# ptmini.net
KiCad netlist of a schematic drawn in EAGLE
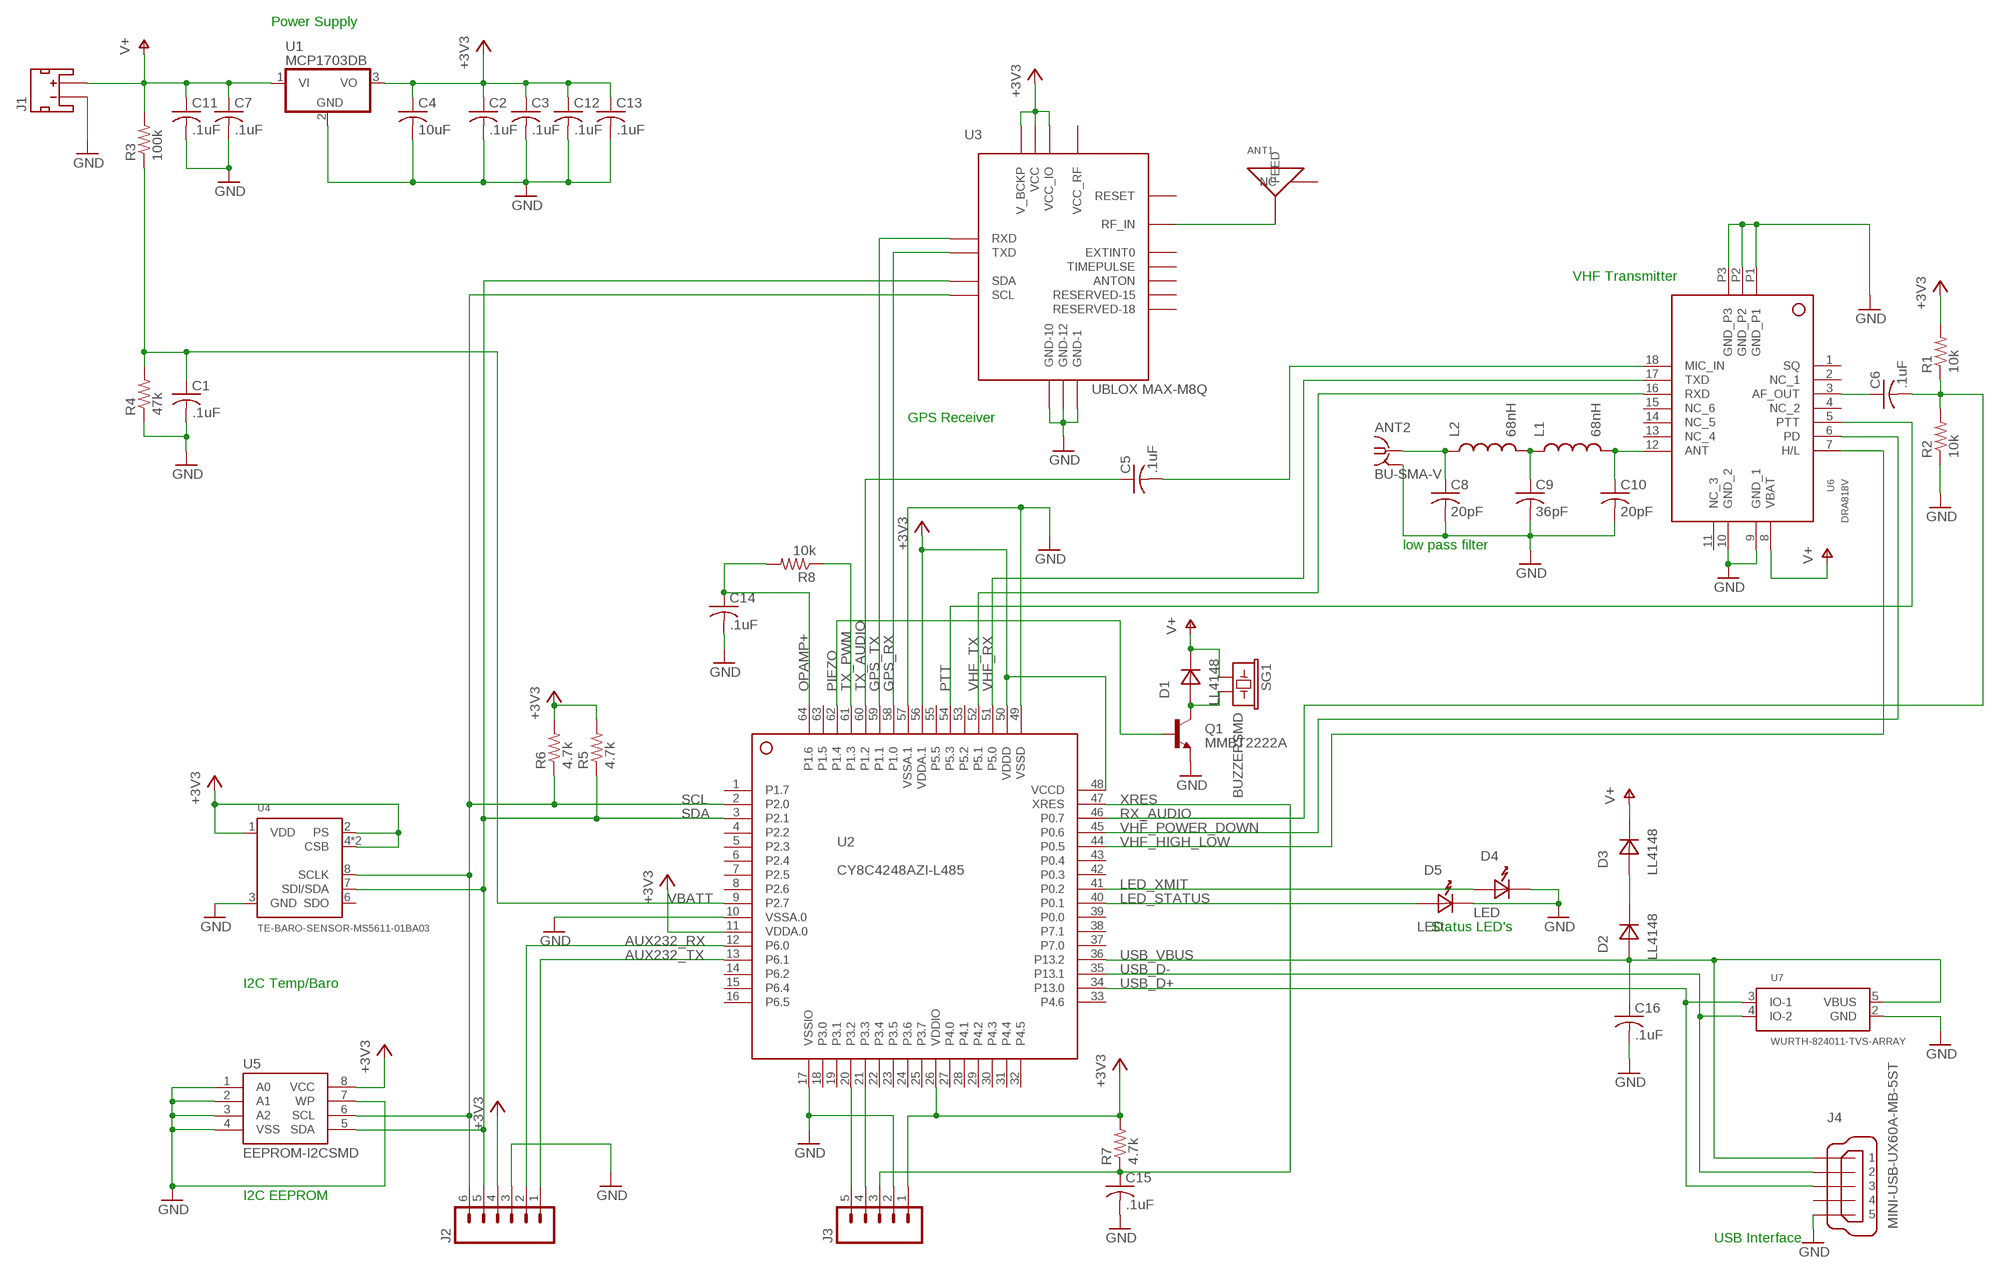
[diagram p0: schematic, sheet 1]

(export (version "E")
  (design (tool "Eeschema 10.0.6"))
  (components
    (comp (ref "ANT1")
      (value "GPS_ANT_SMDBAR")
      (footprint "eagle-import:1575AT43A40")
      (libsource (lib "eagle-import") (part "GPS_ANT_SMDBAR"))
    )
    (comp (ref "ANT2")
      (value "BU-SMA-V")
      (footprint "eagle-import:BU-SMA-V")
      (libsource (lib "eagle-import") (part "BU-SMA-V"))
    )
    (comp (ref "C1")
      (value ".1uF")
      (footprint "eagle-import:C0805")
      (libsource (lib "eagle-import") (part "C-USC0805"))
    )
    (comp (ref "C2")
      (value ".1uF")
      (footprint "eagle-import:C0805")
      (libsource (lib "eagle-import") (part "C-USC0805"))
    )
    (comp (ref "C3")
      (value ".1uF")
      (footprint "eagle-import:C0805")
      (libsource (lib "eagle-import") (part "C-USC0805"))
    )
    (comp (ref "C4")
      (value "10uF")
      (footprint "eagle-import:C0805")
      (libsource (lib "eagle-import") (part "C-USC0805"))
    )
    (comp (ref "C5")
      (value ".1uF")
      (footprint "eagle-import:C0805")
      (libsource (lib "eagle-import") (part "C-USC0805"))
    )
    (comp (ref "C6")
      (value ".1uF")
      (footprint "eagle-import:C0805")
      (libsource (lib "eagle-import") (part "C-USC0805"))
    )
    (comp (ref "C7")
      (value ".1uF")
      (footprint "eagle-import:C0805")
      (libsource (lib "eagle-import") (part "C-USC0805"))
    )
    (comp (ref "C8")
      (value "20pF")
      (footprint "eagle-import:C0805")
      (libsource (lib "eagle-import") (part "C-USC0805"))
    )
    (comp (ref "C9")
      (value "36pF")
      (footprint "eagle-import:C0805")
      (libsource (lib "eagle-import") (part "C-USC0805"))
    )
    (comp (ref "C10")
      (value "20pF")
      (footprint "eagle-import:C0805")
      (libsource (lib "eagle-import") (part "C-USC0805"))
    )
    (comp (ref "C11")
      (value ".1uF")
      (footprint "eagle-import:C0805")
      (libsource (lib "eagle-import") (part "C-USC0805"))
    )
    (comp (ref "C12")
      (value ".1uF")
      (footprint "eagle-import:C0805")
      (libsource (lib "eagle-import") (part "C-USC0805"))
    )
    (comp (ref "C13")
      (value ".1uF")
      (footprint "eagle-import:C0805")
      (libsource (lib "eagle-import") (part "C-USC0805"))
    )
    (comp (ref "C14")
      (value ".1uF")
      (footprint "eagle-import:C0805")
      (libsource (lib "eagle-import") (part "C-USC0805"))
    )
    (comp (ref "C15")
      (value ".1uF")
      (footprint "eagle-import:C0805")
      (libsource (lib "eagle-import") (part "C-USC0805"))
    )
    (comp (ref "C16")
      (value ".1uF")
      (footprint "eagle-import:C0805")
      (libsource (lib "eagle-import") (part "C-USC0805"))
    )
    (comp (ref "D1")
      (value "LL4148")
      (footprint "eagle-import:SOD-80")
      (libsource (lib "eagle-import") (part "LL4148"))
    )
    (comp (ref "D2")
      (value "LL4148")
      (footprint "eagle-import:SOD-80")
      (libsource (lib "eagle-import") (part "LL4148"))
    )
    (comp (ref "D3")
      (value "LL4148")
      (footprint "eagle-import:SOD-80")
      (libsource (lib "eagle-import") (part "LL4148"))
    )
    (comp (ref "D4")
      (value "LED")
      (footprint "eagle-import:DIODE-1206")
      (libsource (lib "eagle-import") (part "LED"))
    )
    (comp (ref "D5")
      (value "LED")
      (footprint "eagle-import:DIODE-1206")
      (libsource (lib "eagle-import") (part "LED"))
    )
    (comp (ref "J1")
      (value "JST_2MM_MALE")
      (footprint "eagle-import:JST-2-SMD")
      (libsource (lib "eagle-import") (part "JST_2MM_MALE"))
    )
    (comp (ref "J2")
      (value "M06RA")
      (footprint "eagle-import:MOLEX-1X6-RA")
      (libsource (lib "eagle-import") (part "M06RA"))
    )
    (comp (ref "J3")
      (value "M05LOCK")
      (footprint "eagle-import:1X05_LOCK")
      (libsource (lib "eagle-import") (part "M05LOCK"))
    )
    (comp (ref "J4")
      (value "MINI-USB-UX60A-MB-5ST")
      (footprint "eagle-import:UX60A-MB-5ST")
      (libsource (lib "eagle-import") (part "MINI-USB-UX60A-MB-5ST"))
    )
    (comp (ref "L1")
      (value "68nH")
      (footprint "eagle-import:0805")
      (libsource (lib "eagle-import") (part "INDUCTOR0805"))
    )
    (comp (ref "L2")
      (value "68nH")
      (footprint "eagle-import:0805")
      (libsource (lib "eagle-import") (part "INDUCTOR0805"))
    )
    (comp (ref "Q1")
      (value "MMBT2222A")
      (footprint "eagle-import:SOT23")
      (libsource (lib "eagle-import") (part "TRANSISTOR_NPNMMBT2222A"))
    )
    (comp (ref "R1")
      (value "10k")
      (footprint "eagle-import:R0805")
      (libsource (lib "eagle-import") (part "R-US_R0805"))
    )
    (comp (ref "R2")
      (value "10k")
      (footprint "eagle-import:R0805")
      (libsource (lib "eagle-import") (part "R-US_R0805"))
    )
    (comp (ref "R3")
      (value "100k")
      (footprint "eagle-import:R0805")
      (libsource (lib "eagle-import") (part "R-US_R0805"))
    )
    (comp (ref "R4")
      (value "47k")
      (footprint "eagle-import:R0805")
      (libsource (lib "eagle-import") (part "R-US_R0805"))
    )
    (comp (ref "R5")
      (value "4.7k")
      (footprint "eagle-import:R0805")
      (libsource (lib "eagle-import") (part "R-US_R0805"))
    )
    (comp (ref "R6")
      (value "4.7k")
      (footprint "eagle-import:R0805")
      (libsource (lib "eagle-import") (part "R-US_R0805"))
    )
    (comp (ref "R7")
      (value "4.7k")
      (footprint "eagle-import:R0805")
      (libsource (lib "eagle-import") (part "R-US_R0805"))
    )
    (comp (ref "R8")
      (value "10k")
      (footprint "eagle-import:R0805")
      (libsource (lib "eagle-import") (part "R-US_R0805"))
    )
    (comp (ref "SG1")
      (value "BUZZERSMD")
      (footprint "eagle-import:BUZZER-CMT1603")
      (libsource (lib "eagle-import") (part "BUZZERSMD"))
    )
    (comp (ref "U1")
      (value "MCP1703DB")
      (footprint "eagle-import:SOT223")
      (libsource (lib "eagle-import") (part "MCP1703DB"))
    )
    (comp (ref "U2")
      (value "CY8C4248AZI-L485")
      (footprint "eagle-import:TQFP64-10X10")
      (libsource (lib "eagle-import") (part "CY8C4248AZI-L485"))
    )
    (comp (ref "U3")
      (value "UBLOX MAX-M8Q")
      (footprint "eagle-import:UBLOX-MAX")
      (libsource (lib "eagle-import") (part "UBLOX-MAX"))
    )
    (comp (ref "U4")
      (value "TE-BARO-SENSOR-MS5611-01BA03")
      (footprint "eagle-import:TE-BARO-SENSOR-MS5611-01BA3")
      (libsource (lib "eagle-import") (part "TE-BARO-SENSOR-MS5611-01BA03"))
    )
    (comp (ref "U5")
      (value "EEPROM-I2CSMD")
      (footprint "eagle-import:SO08")
      (libsource (lib "eagle-import") (part "EEPROM-I2CSMD"))
    )
    (comp (ref "U6")
      (value "DRA818V")
      (footprint "eagle-import:SMD_DRA818")
      (libsource (lib "eagle-import") (part "DRA818V"))
    )
    (comp (ref "U7")
      (value "WURTH-824011-TVS-ARRAY")
      (footprint "eagle-import:SOT23-5")
      (libsource (lib "eagle-import") (part "WURTH-824011-TVS-ARRAY"))
    )
  )
  (nets
    (net (code "1") (name "+3V3") (class "Default")
      (node (ref "C12") (pin "1") (pinfunction "1_1") (pintype "passive"))
      (node (ref "C13") (pin "1") (pinfunction "1_1") (pintype "passive"))
      (node (ref "C2") (pin "1") (pinfunction "1_1") (pintype "passive"))
      (node (ref "C3") (pin "1") (pinfunction "1_1") (pintype "passive"))
      (node (ref "C4") (pin "1") (pinfunction "1_1") (pintype "passive"))
      (node (ref "J2") (pin "4") (pinfunction "4_4") (pintype "passive"))
      (node (ref "J3") (pin "1") (pinfunction "1_1") (pintype "passive"))
      (node (ref "R1") (pin "2") (pinfunction "2_2") (pintype "passive"))
      (node (ref "R5") (pin "2") (pinfunction "2_2") (pintype "passive"))
      (node (ref "R6") (pin "2") (pinfunction "2_2") (pintype "passive"))
      (node (ref "R7") (pin "2") (pinfunction "2_2") (pintype "passive"))
      (node (ref "U1") (pin "3") (pinfunction "VO_3") (pintype "passive"))
      (node (ref "U2") (pin "11") (pinfunction "VDDA.0_11") (pintype "power_in"))
      (node (ref "U2") (pin "26") (pinfunction "VDDIO_26") (pintype "power_in"))
      (node (ref "U2") (pin "48") (pinfunction "VCCD_48") (pintype "power_in"))
      (node (ref "U2") (pin "50") (pinfunction "VDDD_50") (pintype "power_in"))
      (node (ref "U2") (pin "56") (pinfunction "VDDA.1_56") (pintype "power_in"))
      (node (ref "U3") (pin "6_V_BCKP") (pinfunction "V_BCKP_6_V_BCKP") (pintype "bidirectional"))
      (node (ref "U3") (pin "7_VCC_IO") (pinfunction "VCC_IO_7_VCC_IO") (pintype "power_in"))
      (node (ref "U3") (pin "8_VCC") (pinfunction "VCC_8_VCC") (pintype "power_in"))
      (node (ref "U4") (pin "1") (pinfunction "VDD_1") (pintype "power_in"))
      (node (ref "U4") (pin "2") (pinfunction "PS_2") (pintype "bidirectional"))
      (node (ref "U4") (pin "4") (pinfunction "CSB_4") (pintype "bidirectional"))
      (node (ref "U4") (pin "5") (pinfunction "CSB_5") (pintype "bidirectional"))
      (node (ref "U5") (pin "8") (pinfunction "VCC_8") (pintype "power_in"))
    )
    (net (code "2") (name "/AUX232_RX") (class "Default")
      (node (ref "J2") (pin "2") (pinfunction "2_2") (pintype "passive"))
      (node (ref "U2") (pin "12") (pinfunction "P6.0_12") (pintype "bidirectional"))
    )
    (net (code "3") (name "/AUX232_TX") (class "Default")
      (node (ref "J2") (pin "1") (pinfunction "1_1") (pintype "passive"))
      (node (ref "U2") (pin "13") (pinfunction "P6.1_13") (pintype "bidirectional"))
    )
    (net (code "4") (name "/GPS_RX") (class "Default")
      (node (ref "U2") (pin "58") (pinfunction "P1.0_58") (pintype "bidirectional"))
      (node (ref "U3") (pin "2_TXD1") (pinfunction "TXD_2_TXD1") (pintype "bidirectional"))
    )
    (net (code "5") (name "/GPS_TX") (class "Default")
      (node (ref "U2") (pin "59") (pinfunction "P1.1_59") (pintype "bidirectional"))
      (node (ref "U3") (pin "3_RXD1") (pinfunction "RXD_3_RXD1") (pintype "bidirectional"))
    )
    (net (code "6") (name "/LED_STATUS") (class "Default")
      (node (ref "D5") (pin "ANODE") (pinfunction "ANODE_ANODE") (pintype "passive"))
      (node (ref "U2") (pin "40") (pinfunction "P0.1_40") (pintype "bidirectional"))
    )
    (net (code "7") (name "/LED_XMIT") (class "Default")
      (node (ref "D4") (pin "ANODE") (pinfunction "ANODE_ANODE") (pintype "passive"))
      (node (ref "U2") (pin "41") (pinfunction "P0.2_41") (pintype "bidirectional"))
    )
    (net (code "8") (name "/OPAMP+") (class "Default")
      (node (ref "C14") (pin "1") (pinfunction "1_1") (pintype "passive"))
      (node (ref "R8") (pin "2") (pinfunction "2_2") (pintype "passive"))
      (node (ref "U2") (pin "64") (pinfunction "P1.6_64") (pintype "bidirectional"))
    )
    (net (code "9") (name "/PIEZO") (class "Default")
      (node (ref "Q1") (pin "1") (pinfunction "B_1") (pintype "passive"))
      (node (ref "U2") (pin "62") (pinfunction "P1.4_62") (pintype "bidirectional"))
    )
    (net (code "10") (name "/PTT") (class "Default")
      (node (ref "U2") (pin "54") (pinfunction "P5.3_54") (pintype "bidirectional"))
      (node (ref "U6") (pin "5") (pinfunction "PTT_5") (pintype "bidirectional"))
    )
    (net (code "11") (name "/RESET") (class "Default")
      (node (ref "U3") (pin "9_V_RESET") (pinfunction "RESET_9_V_RESET") (pintype "power_in"))
    )
    (net (code "12") (name "/RX_AUDIO") (class "Default")
      (node (ref "C6") (pin "2") (pinfunction "2_2") (pintype "passive"))
      (node (ref "R1") (pin "1") (pinfunction "1_1") (pintype "passive"))
      (node (ref "R2") (pin "2") (pinfunction "2_2") (pintype "passive"))
      (node (ref "U2") (pin "46") (pinfunction "P0.7_46") (pintype "bidirectional"))
    )
    (net (code "13") (name "/SCL") (class "Default")
      (node (ref "J2") (pin "6") (pinfunction "6_6") (pintype "passive"))
      (node (ref "R6") (pin "1") (pinfunction "1_1") (pintype "passive"))
      (node (ref "U2") (pin "2") (pinfunction "P2.0_2") (pintype "bidirectional"))
      (node (ref "U3") (pin "17_SCL2") (pinfunction "SCL_17_SCL2") (pintype "bidirectional"))
      (node (ref "U4") (pin "8") (pinfunction "SCLK_8") (pintype "bidirectional"))
      (node (ref "U5") (pin "6") (pinfunction "SCL_6") (pintype "bidirectional"))
    )
    (net (code "14") (name "/SDA") (class "Default")
      (node (ref "J2") (pin "5") (pinfunction "5_5") (pintype "passive"))
      (node (ref "R5") (pin "1") (pinfunction "1_1") (pintype "passive"))
      (node (ref "U2") (pin "3") (pinfunction "P2.1_3") (pintype "bidirectional"))
      (node (ref "U3") (pin "16_SDA2") (pinfunction "SDA_16_SDA2") (pintype "bidirectional"))
      (node (ref "U4") (pin "7") (pinfunction "SDI/SDA_7") (pintype "bidirectional"))
      (node (ref "U5") (pin "5") (pinfunction "SDA_5") (pintype "bidirectional"))
    )
    (net (code "15") (name "/TX_AUDIO") (class "Default")
      (node (ref "C5") (pin "1") (pinfunction "1_1") (pintype "passive"))
      (node (ref "U2") (pin "60") (pinfunction "P1.2_60") (pintype "bidirectional"))
    )
    (net (code "16") (name "/TX_PWM") (class "Default")
      (node (ref "R8") (pin "1") (pinfunction "1_1") (pintype "passive"))
      (node (ref "U2") (pin "61") (pinfunction "P1.3_61") (pintype "bidirectional"))
    )
    (net (code "17") (name "/USB_D+") (class "Default")
      (node (ref "J4") (pin "3") (pinfunction "3_3") (pintype "input"))
      (node (ref "U2") (pin "34") (pinfunction "P13.0_34") (pintype "bidirectional"))
      (node (ref "U7") (pin "3") (pinfunction "IO-1_3") (pintype "bidirectional"))
    )
    (net (code "18") (name "/USB_D-") (class "Default")
      (node (ref "J4") (pin "2") (pinfunction "2_2") (pintype "input"))
      (node (ref "U2") (pin "35") (pinfunction "P13.1_35") (pintype "bidirectional"))
      (node (ref "U7") (pin "4") (pinfunction "IO-2_4") (pintype "bidirectional"))
    )
    (net (code "19") (name "/USB_VBUS") (class "Default")
      (node (ref "C16") (pin "1") (pinfunction "1_1") (pintype "passive"))
      (node (ref "D2") (pin "ANODE") (pinfunction "ANODE_ANODE") (pintype "passive"))
      (node (ref "J4") (pin "1") (pinfunction "1_1") (pintype "input"))
      (node (ref "U2") (pin "36") (pinfunction "P13.2_36") (pintype "bidirectional"))
      (node (ref "U7") (pin "5") (pinfunction "VBUS_5") (pintype "bidirectional"))
    )
    (net (code "20") (name "/VBATT") (class "Default")
      (node (ref "C1") (pin "1") (pinfunction "1_1") (pintype "passive"))
      (node (ref "R3") (pin "1") (pinfunction "1_1") (pintype "passive"))
      (node (ref "R4") (pin "2") (pinfunction "2_2") (pintype "passive"))
      (node (ref "U2") (pin "9") (pinfunction "P2.7_9") (pintype "bidirectional"))
    )
    (net (code "21") (name "/VHF_HIGH_LOW") (class "Default")
      (node (ref "U2") (pin "44") (pinfunction "P0.5_44") (pintype "bidirectional"))
      (node (ref "U6") (pin "7") (pinfunction "H/L_7") (pintype "bidirectional"))
    )
    (net (code "22") (name "/VHF_POWER_DOWN") (class "Default")
      (node (ref "U2") (pin "45") (pinfunction "P0.6_45") (pintype "bidirectional"))
      (node (ref "U6") (pin "6") (pinfunction "PD_6") (pintype "bidirectional"))
    )
    (net (code "23") (name "/VHF_RX") (class "Default")
      (node (ref "U2") (pin "51") (pinfunction "P5.0_51") (pintype "bidirectional"))
      (node (ref "U6") (pin "17") (pinfunction "TXD_17") (pintype "bidirectional"))
    )
    (net (code "24") (name "/VHF_TX") (class "Default")
      (node (ref "U2") (pin "52") (pinfunction "P5.1_52") (pintype "bidirectional"))
      (node (ref "U6") (pin "16") (pinfunction "RXD_16") (pintype "bidirectional"))
    )
    (net (code "25") (name "/XRES") (class "Default")
      (node (ref "C15") (pin "1") (pinfunction "1_1") (pintype "passive"))
      (node (ref "J3") (pin "3") (pinfunction "3_3") (pintype "passive"))
      (node (ref "R7") (pin "1") (pinfunction "1_1") (pintype "passive"))
      (node (ref "U2") (pin "47") (pinfunction "XRES_47") (pintype "input"))
    )
    (net (code "26") (name "GND") (class "Default")
      (node (ref "ANT2") (pin "2") (pinfunction "2_2") (pintype "passive"))
      (node (ref "ANT2") (pin "3") (pinfunction "2_3") (pintype "passive"))
      (node (ref "ANT2") (pin "4") (pinfunction "2_4") (pintype "passive"))
      (node (ref "ANT2") (pin "5") (pinfunction "2_5") (pintype "passive"))
      (node (ref "C1") (pin "2") (pinfunction "2_2") (pintype "passive"))
      (node (ref "C10") (pin "2") (pinfunction "2_2") (pintype "passive"))
      (node (ref "C11") (pin "2") (pinfunction "2_2") (pintype "passive"))
      (node (ref "C12") (pin "2") (pinfunction "2_2") (pintype "passive"))
      (node (ref "C13") (pin "2") (pinfunction "2_2") (pintype "passive"))
      (node (ref "C14") (pin "2") (pinfunction "2_2") (pintype "passive"))
      (node (ref "C15") (pin "2") (pinfunction "2_2") (pintype "passive"))
      (node (ref "C16") (pin "2") (pinfunction "2_2") (pintype "passive"))
      (node (ref "C2") (pin "2") (pinfunction "2_2") (pintype "passive"))
      (node (ref "C3") (pin "2") (pinfunction "2_2") (pintype "passive"))
      (node (ref "C4") (pin "2") (pinfunction "2_2") (pintype "passive"))
      (node (ref "C7") (pin "2") (pinfunction "2_2") (pintype "passive"))
      (node (ref "C8") (pin "2") (pinfunction "2_2") (pintype "passive"))
      (node (ref "C9") (pin "2") (pinfunction "2_2") (pintype "passive"))
      (node (ref "D4") (pin "CATHODE") (pinfunction "CATHODE_CATHODE") (pintype "passive"))
      (node (ref "D5") (pin "CATHODE") (pinfunction "CATHODE_CATHODE") (pintype "passive"))
      (node (ref "J1") (pin "1") (pinfunction "-_1") (pintype "bidirectional"))
      (node (ref "J2") (pin "3") (pinfunction "3_3") (pintype "passive"))
      (node (ref "J3") (pin "2") (pinfunction "2_2") (pintype "passive"))
      (node (ref "J4") (pin "5") (pinfunction "5_5") (pintype "input"))
      (node (ref "Q1") (pin "2") (pinfunction "E_2") (pintype "passive"))
      (node (ref "R2") (pin "1") (pinfunction "1_1") (pintype "passive"))
      (node (ref "R4") (pin "1") (pinfunction "1_1") (pintype "passive"))
      (node (ref "U1") (pin "2") (pinfunction "GND_2") (pintype "passive"))
      (node (ref "U2") (pin "10") (pinfunction "VSSA.0_10") (pintype "power_in"))
      (node (ref "U2") (pin "17") (pinfunction "VSSIO_17") (pintype "power_in"))
      (node (ref "U2") (pin "49") (pinfunction "VSSD_49") (pintype "power_in"))
      (node (ref "U2") (pin "57") (pinfunction "VSSA.1_57") (pintype "power_in"))
      (node (ref "U3") (pin "10_GND") (pinfunction "GND-10_10_GND") (pintype "power_in"))
      (node (ref "U3") (pin "12_GND") (pinfunction "GND-12_12_GND") (pintype "power_in"))
      (node (ref "U3") (pin "1_GND") (pinfunction "GND-1_1_GND") (pintype "power_in"))
      (node (ref "U4") (pin "3") (pinfunction "GND_3") (pintype "power_in"))
      (node (ref "U5") (pin "1") (pinfunction "A0_1") (pintype "bidirectional"))
      (node (ref "U5") (pin "2") (pinfunction "A1_2") (pintype "bidirectional"))
      (node (ref "U5") (pin "3") (pinfunction "A2_3") (pintype "bidirectional"))
      (node (ref "U5") (pin "4") (pinfunction "VSS_4") (pintype "power_in"))
      (node (ref "U5") (pin "7") (pinfunction "WP_7") (pintype "bidirectional"))
      (node (ref "U6") (pin "10") (pinfunction "GND_2_10") (pintype "bidirectional"))
      (node (ref "U6") (pin "9") (pinfunction "GND_1_9") (pintype "bidirectional"))
      (node (ref "U6") (pin "P1") (pinfunction "GND_P1_P1") (pintype "bidirectional"))
      (node (ref "U6") (pin "P2") (pinfunction "GND_P2_P2") (pintype "bidirectional"))
      (node (ref "U6") (pin "P3") (pinfunction "GND_P3_P3") (pintype "bidirectional"))
      (node (ref "U7") (pin "2") (pinfunction "GND_2") (pintype "power_in"))
    )
    (net (code "27") (name "Net-(ANT2-Pad1)") (class "Default")
      (node (ref "ANT2") (pin "1") (pinfunction "1_1") (pintype "passive"))
      (node (ref "C8") (pin "1") (pinfunction "1_1") (pintype "passive"))
      (node (ref "L2") (pin "1") (pinfunction "1_1") (pintype "passive"))
    )
    (net (code "28") (name "Net-(C9-Pad1)") (class "Default")
      (node (ref "C9") (pin "1") (pinfunction "1_1") (pintype "passive"))
      (node (ref "L1") (pin "1") (pinfunction "1_1") (pintype "passive"))
      (node (ref "L2") (pin "2") (pinfunction "2_2") (pintype "passive"))
    )
    (net (code "29") (name "Net-(D2-PadCATHODE)") (class "Default")
      (node (ref "D2") (pin "CATHODE") (pinfunction "CATHODE_CATHODE") (pintype "passive"))
      (node (ref "D3") (pin "ANODE") (pinfunction "ANODE_ANODE") (pintype "passive"))
    )
    (net (code "30") (name "Net-(Q1-C)") (class "Default")
      (node (ref "D1") (pin "ANODE") (pinfunction "ANODE_ANODE") (pintype "passive"))
      (node (ref "Q1") (pin "3") (pinfunction "C_3") (pintype "passive"))
      (node (ref "SG1") (pin "P$2") (pinfunction "2_P$2") (pintype "passive"))
    )
    (net (code "31") (name "Net-(U2-P3.2)") (class "Default")
      (node (ref "J3") (pin "5") (pinfunction "5_5") (pintype "passive"))
      (node (ref "U2") (pin "20") (pinfunction "P3.2_20") (pintype "bidirectional"))
    )
    (net (code "32") (name "Net-(U2-P3.3)") (class "Default")
      (node (ref "J3") (pin "4") (pinfunction "4_4") (pintype "passive"))
      (node (ref "U2") (pin "21") (pinfunction "P3.3_21") (pintype "bidirectional"))
    )
    (net (code "33") (name "Net-(U3-RF_IN)") (class "Default")
      (node (ref "ANT1") (pin "FEED") (pinfunction "FEED_FEED") (pintype "bidirectional"))
      (node (ref "U3") (pin "11_RF_IN") (pinfunction "RF_IN_11_RF_IN") (pintype "bidirectional"))
    )
    (net (code "34") (name "Net-(U6-AF_OUT)") (class "Default")
      (node (ref "C6") (pin "1") (pinfunction "1_1") (pintype "passive"))
      (node (ref "U6") (pin "3") (pinfunction "AF_OUT_3") (pintype "bidirectional"))
    )
    (net (code "35") (name "Net-(U6-ANT)") (class "Default")
      (node (ref "C10") (pin "1") (pinfunction "1_1") (pintype "passive"))
      (node (ref "L1") (pin "2") (pinfunction "2_2") (pintype "passive"))
      (node (ref "U6") (pin "12") (pinfunction "ANT_12") (pintype "bidirectional"))
    )
    (net (code "36") (name "Net-(U6-MIC_IN)") (class "Default")
      (node (ref "C5") (pin "2") (pinfunction "2_2") (pintype "passive"))
      (node (ref "U6") (pin "18") (pinfunction "MIC_IN_18") (pintype "bidirectional"))
    )
    (net (code "37") (name "V+") (class "Default")
      (node (ref "C11") (pin "1") (pinfunction "1_1") (pintype "passive"))
      (node (ref "C7") (pin "1") (pinfunction "1_1") (pintype "passive"))
      (node (ref "D1") (pin "CATHODE") (pinfunction "CATHODE_CATHODE") (pintype "passive"))
      (node (ref "D3") (pin "CATHODE") (pinfunction "CATHODE_CATHODE") (pintype "passive"))
      (node (ref "J1") (pin "2") (pinfunction "+_2") (pintype "bidirectional"))
      (node (ref "R3") (pin "2") (pinfunction "2_2") (pintype "passive"))
      (node (ref "SG1") (pin "P$1") (pinfunction "1_P$1") (pintype "passive"))
      (node (ref "U1") (pin "1") (pinfunction "VI_1") (pintype "input"))
      (node (ref "U6") (pin "8") (pinfunction "VBAT_8") (pintype "bidirectional"))
    )
    (net (code "38") (name "unconnected-(ANT1-PadNC)") (class "Default")
      (node (ref "ANT1") (pin "NC") (pinfunction "NC_NC") (pintype "bidirectional"))
    )
    (net (code "39") (name "unconnected-(J1-PAD1-PadNC1)") (class "Default")
      (node (ref "J1") (pin "NC1") (pinfunction "PAD1_NC1") (pintype "bidirectional"))
    )
    (net (code "40") (name "unconnected-(J1-PAD2-PadNC2)") (class "Default")
      (node (ref "J1") (pin "NC2") (pinfunction "PAD2_NC2") (pintype "bidirectional"))
    )
    (net (code "41") (name "unconnected-(J4-Pad4)") (class "Default")
      (node (ref "J4") (pin "4") (pinfunction "4_4") (pintype "input"))
    )
    (net (code "42") (name "unconnected-(U2-P0.0-Pad39)") (class "Default")
      (node (ref "U2") (pin "39") (pinfunction "P0.0_39") (pintype "bidirectional"))
    )
    (net (code "43") (name "unconnected-(U2-P0.3-Pad42)") (class "Default")
      (node (ref "U2") (pin "42") (pinfunction "P0.3_42") (pintype "bidirectional"))
    )
    (net (code "44") (name "unconnected-(U2-P0.4-Pad43)") (class "Default")
      (node (ref "U2") (pin "43") (pinfunction "P0.4_43") (pintype "bidirectional"))
    )
    (net (code "45") (name "unconnected-(U2-P1.5-Pad63)") (class "Default")
      (node (ref "U2") (pin "63") (pinfunction "P1.5_63") (pintype "bidirectional"))
    )
    (net (code "46") (name "unconnected-(U2-P1.7-Pad1)") (class "Default")
      (node (ref "U2") (pin "1") (pinfunction "P1.7_1") (pintype "bidirectional"))
    )
    (net (code "47") (name "unconnected-(U2-P2.2-Pad4)") (class "Default")
      (node (ref "U2") (pin "4") (pinfunction "P2.2_4") (pintype "bidirectional"))
    )
    (net (code "48") (name "unconnected-(U2-P2.3-Pad5)") (class "Default")
      (node (ref "U2") (pin "5") (pinfunction "P2.3_5") (pintype "bidirectional"))
    )
    (net (code "49") (name "unconnected-(U2-P2.4-Pad6)") (class "Default")
      (node (ref "U2") (pin "6") (pinfunction "P2.4_6") (pintype "bidirectional"))
    )
    (net (code "50") (name "unconnected-(U2-P2.5-Pad7)") (class "Default")
      (node (ref "U2") (pin "7") (pinfunction "P2.5_7") (pintype "bidirectional"))
    )
    (net (code "51") (name "unconnected-(U2-P2.6-Pad8)") (class "Default")
      (node (ref "U2") (pin "8") (pinfunction "P2.6_8") (pintype "bidirectional"))
    )
    (net (code "52") (name "unconnected-(U2-P3.0-Pad18)") (class "Default")
      (node (ref "U2") (pin "18") (pinfunction "P3.0_18") (pintype "bidirectional"))
    )
    (net (code "53") (name "unconnected-(U2-P3.1-Pad19)") (class "Default")
      (node (ref "U2") (pin "19") (pinfunction "P3.1_19") (pintype "bidirectional"))
    )
    (net (code "54") (name "unconnected-(U2-P3.4-Pad22)") (class "Default")
      (node (ref "U2") (pin "22") (pinfunction "P3.4_22") (pintype "bidirectional"))
    )
    (net (code "55") (name "unconnected-(U2-P3.5-Pad23)") (class "Default")
      (node (ref "U2") (pin "23") (pinfunction "P3.5_23") (pintype "bidirectional"))
    )
    (net (code "56") (name "unconnected-(U2-P3.6-Pad24)") (class "Default")
      (node (ref "U2") (pin "24") (pinfunction "P3.6_24") (pintype "bidirectional"))
    )
    (net (code "57") (name "unconnected-(U2-P3.7-Pad25)") (class "Default")
      (node (ref "U2") (pin "25") (pinfunction "P3.7_25") (pintype "bidirectional"))
    )
    (net (code "58") (name "unconnected-(U2-P4.0-Pad27)") (class "Default")
      (node (ref "U2") (pin "27") (pinfunction "P4.0_27") (pintype "bidirectional"))
    )
    (net (code "59") (name "unconnected-(U2-P4.1-Pad28)") (class "Default")
      (node (ref "U2") (pin "28") (pinfunction "P4.1_28") (pintype "bidirectional"))
    )
    (net (code "60") (name "unconnected-(U2-P4.2-Pad29)") (class "Default")
      (node (ref "U2") (pin "29") (pinfunction "P4.2_29") (pintype "bidirectional"))
    )
    (net (code "61") (name "unconnected-(U2-P4.3-Pad30)") (class "Default")
      (node (ref "U2") (pin "30") (pinfunction "P4.3_30") (pintype "bidirectional"))
    )
    (net (code "62") (name "unconnected-(U2-P4.4-Pad31)") (class "Default")
      (node (ref "U2") (pin "31") (pinfunction "P4.4_31") (pintype "bidirectional"))
    )
    (net (code "63") (name "unconnected-(U2-P4.5-Pad32)") (class "Default")
      (node (ref "U2") (pin "32") (pinfunction "P4.5_32") (pintype "bidirectional"))
    )
    (net (code "64") (name "unconnected-(U2-P4.6-Pad33)") (class "Default")
      (node (ref "U2") (pin "33") (pinfunction "P4.6_33") (pintype "bidirectional"))
    )
    (net (code "65") (name "unconnected-(U2-P5.2-Pad53)") (class "Default")
      (node (ref "U2") (pin "53") (pinfunction "P5.2_53") (pintype "bidirectional"))
    )
    (net (code "66") (name "unconnected-(U2-P5.5-Pad55)") (class "Default")
      (node (ref "U2") (pin "55") (pinfunction "P5.5_55") (pintype "bidirectional"))
    )
    (net (code "67") (name "unconnected-(U2-P6.2-Pad14)") (class "Default")
      (node (ref "U2") (pin "14") (pinfunction "P6.2_14") (pintype "bidirectional"))
    )
    (net (code "68") (name "unconnected-(U2-P6.4-Pad15)") (class "Default")
      (node (ref "U2") (pin "15") (pinfunction "P6.4_15") (pintype "bidirectional"))
    )
    (net (code "69") (name "unconnected-(U2-P6.5-Pad16)") (class "Default")
      (node (ref "U2") (pin "16") (pinfunction "P6.5_16") (pintype "bidirectional"))
    )
    (net (code "70") (name "unconnected-(U2-P7.0-Pad37)") (class "Default")
      (node (ref "U2") (pin "37") (pinfunction "P7.0_37") (pintype "bidirectional"))
    )
    (net (code "71") (name "unconnected-(U2-P7.1-Pad38)") (class "Default")
      (node (ref "U2") (pin "38") (pinfunction "P7.1_38") (pintype "bidirectional"))
    )
    (net (code "72") (name "unconnected-(U3-ANTON-Pad13_ANTON)") (class "Default")
      (node (ref "U3") (pin "13_ANTON") (pinfunction "ANTON_13_ANTON") (pintype "bidirectional"))
    )
    (net (code "73") (name "unconnected-(U3-EXTINT0-Pad5_EXTINT0)") (class "Default")
      (node (ref "U3") (pin "5_EXTINT0") (pinfunction "EXTINT0_5_EXTINT0") (pintype "bidirectional"))
    )
    (net (code "74") (name "unconnected-(U3-RESERVED-15-Pad15_RESERVED)") (class "Default")
      (node (ref "U3") (pin "15_RESERVED") (pinfunction "RESERVED-15_15_RESERVED") (pintype "bidirectional"))
    )
    (net (code "75") (name "unconnected-(U3-RESERVED-18-Pad18_RESERVED)") (class "Default")
      (node (ref "U3") (pin "18_RESERVED") (pinfunction "RESERVED-18_18_RESERVED") (pintype "bidirectional"))
    )
    (net (code "76") (name "unconnected-(U3-TIMEPULSE-Pad4_TIMEPULSE)") (class "Default")
      (node (ref "U3") (pin "4_TIMEPULSE") (pinfunction "TIMEPULSE_4_TIMEPULSE") (pintype "bidirectional"))
    )
    (net (code "77") (name "unconnected-(U3-VCC_RF-Pad14_VCC_RF)") (class "Default")
      (node (ref "U3") (pin "14_VCC_RF") (pinfunction "VCC_RF_14_VCC_RF") (pintype "bidirectional"))
    )
    (net (code "78") (name "unconnected-(U4-SDO-Pad6)") (class "Default")
      (node (ref "U4") (pin "6") (pinfunction "SDO_6") (pintype "bidirectional"))
    )
    (net (code "79") (name "unconnected-(U6-NC_1-Pad2)") (class "Default")
      (node (ref "U6") (pin "2") (pinfunction "NC_1_2") (pintype "bidirectional"))
    )
    (net (code "80") (name "unconnected-(U6-NC_2-Pad4)") (class "Default")
      (node (ref "U6") (pin "4") (pinfunction "NC_2_4") (pintype "bidirectional"))
    )
    (net (code "81") (name "unconnected-(U6-NC_3-Pad11)") (class "Default")
      (node (ref "U6") (pin "11") (pinfunction "NC_3_11") (pintype "bidirectional"))
    )
    (net (code "82") (name "unconnected-(U6-NC_4-Pad13)") (class "Default")
      (node (ref "U6") (pin "13") (pinfunction "NC_4_13") (pintype "bidirectional"))
    )
    (net (code "83") (name "unconnected-(U6-NC_5-Pad14)") (class "Default")
      (node (ref "U6") (pin "14") (pinfunction "NC_5_14") (pintype "bidirectional"))
    )
    (net (code "84") (name "unconnected-(U6-NC_6-Pad15)") (class "Default")
      (node (ref "U6") (pin "15") (pinfunction "NC_6_15") (pintype "bidirectional"))
    )
    (net (code "85") (name "unconnected-(U6-SQ-Pad1)") (class "Default")
      (node (ref "U6") (pin "1") (pinfunction "SQ_1") (pintype "bidirectional"))
    )
  )
)
